# multivibrator.net
KiCad netlist of a schematic drawn in Altium Designer
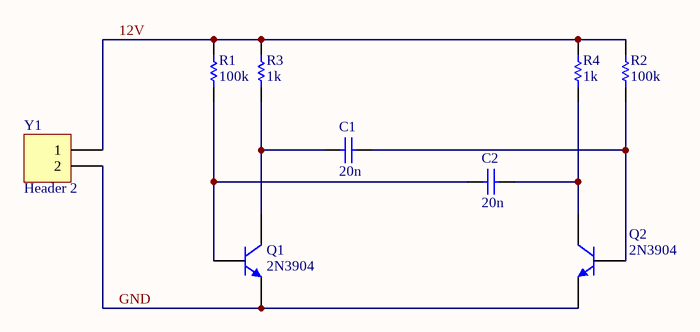
[diagram p0: multivibrator.SchDoc]

(export (version "E")
  (design (tool "Eeschema 10.0.6"))
  (components
    (comp (ref "C1")
      (value "20n")
      (footprint "RAD-0.3")
      (description "Capacitor")
      (fields (field (name "PUBLISHER") "Altium Limited"))
      (libsource (lib "Miscellaneous Devices") (part "Cap"))
    )
    (comp (ref "C2")
      (value "20n")
      (footprint "RAD-0.3")
      (description "Capacitor")
      (fields (field (name "PUBLISHER") "Altium Limited"))
      (libsource (lib "Miscellaneous Devices") (part "Cap"))
    )
    (comp (ref "Q1")
      (value "2N3904")
      (footprint "TO-92A")
      (description "NPN General Purpose Amplifier")
      (fields (field (name "PUBLISHER") "Altium Limited"))
      (libsource (lib "Miscellaneous Devices") (part "2N3904"))
    )
    (comp (ref "Q2")
      (value "2N3904")
      (footprint "TO-92A")
      (description "NPN General Purpose Amplifier")
      (fields (field (name "PUBLISHER") "Altium Limited"))
      (libsource (lib "Miscellaneous Devices") (part "2N3904"))
    )
    (comp (ref "R1")
      (value "100k")
      (footprint "AXIAL-0.3")
      (description "Resistor")
      (fields (field (name "PUBLISHER") "Altium Limited"))
      (libsource (lib "Miscellaneous Devices") (part "Res1"))
    )
    (comp (ref "R2")
      (value "100k")
      (footprint "AXIAL-0.3")
      (description "Resistor")
      (fields (field (name "PUBLISHER") "Altium Limited"))
      (libsource (lib "Miscellaneous Devices") (part "Res1"))
    )
    (comp (ref "R3")
      (value "1k")
      (footprint "AXIAL-0.3")
      (description "Resistor")
      (fields (field (name "PUBLISHER") "Altium Limited"))
      (libsource (lib "Miscellaneous Devices") (part "Res1"))
    )
    (comp (ref "R4")
      (value "1k")
      (footprint "AXIAL-0.3")
      (description "Resistor")
      (fields (field (name "PUBLISHER") "Altium Limited"))
      (libsource (lib "Miscellaneous Devices") (part "Res1"))
    )
    (comp (ref "Y1")
      (value "Header 2")
      (footprint "HDR1X2")
      (description "Header, 2-Pin")
      (fields (field (name "PUBLISHER") "Altium Limited"))
      (libsource (lib "Miscellaneous Connectors") (part "Header 2"))
    )
  )
  (nets
    (net (code "1") (name "/12V") (class "Default")
      (node (ref "R1") (pin "2") (pinfunction "2_2") (pintype "passive"))
      (node (ref "R2") (pin "2") (pinfunction "2_2") (pintype "passive"))
      (node (ref "R3") (pin "2") (pinfunction "2_2") (pintype "passive"))
      (node (ref "R4") (pin "2") (pinfunction "2_2") (pintype "passive"))
      (node (ref "Y1") (pin "1") (pinfunction "1_1") (pintype "passive"))
    )
    (net (code "2") (name "/GND") (class "Default")
      (node (ref "Q1") (pin "1") (pinfunction "E_1") (pintype "passive"))
      (node (ref "Q2") (pin "1") (pinfunction "E_1") (pintype "passive"))
      (node (ref "Y1") (pin "2") (pinfunction "2_2") (pintype "passive"))
    )
    (net (code "3") (name "Net-(Q1-B)") (class "Default")
      (node (ref "C2") (pin "1") (pinfunction "1_1") (pintype "passive"))
      (node (ref "Q1") (pin "2") (pinfunction "B_2") (pintype "passive"))
      (node (ref "R1") (pin "1") (pinfunction "1_1") (pintype "passive"))
    )
    (net (code "4") (name "Net-(Q1-C)") (class "Default")
      (node (ref "C1") (pin "1") (pinfunction "1_1") (pintype "passive"))
      (node (ref "Q1") (pin "3") (pinfunction "C_3") (pintype "passive"))
      (node (ref "R3") (pin "1") (pinfunction "1_1") (pintype "passive"))
    )
    (net (code "5") (name "Net-(Q2-B)") (class "Default")
      (node (ref "C1") (pin "2") (pinfunction "2_2") (pintype "passive"))
      (node (ref "Q2") (pin "2") (pinfunction "B_2") (pintype "passive"))
      (node (ref "R2") (pin "1") (pinfunction "1_1") (pintype "passive"))
    )
    (net (code "6") (name "Net-(Q2-C)") (class "Default")
      (node (ref "C2") (pin "2") (pinfunction "2_2") (pintype "passive"))
      (node (ref "Q2") (pin "3") (pinfunction "C_3") (pintype "passive"))
      (node (ref "R4") (pin "1") (pinfunction "1_1") (pintype "passive"))
    )
  )
)
